# wind_turbine_sc.net
KiCad netlist of a schematic drawn in EAGLE
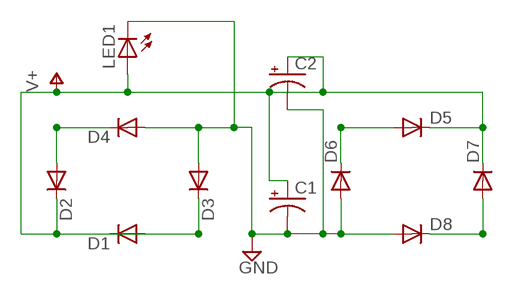
[diagram p0: schematic, sheet 1]

(export (version "E")
  (design (tool "Eeschema 10.0.6"))
  (components
    (comp (ref "C1")
      (value "CAP_POLPTH4")
      (footprint "eagle-import:CPOL-RADIAL-1000UF-25V")
      (libsource (lib "eagle-import") (part "CAP_POLPTH4"))
    )
    (comp (ref "C2")
      (value "CAP_POLPTH4")
      (footprint "eagle-import:CPOL-RADIAL-1000UF-25V")
      (libsource (lib "eagle-import") (part "CAP_POLPTH4"))
    )
    (comp (ref "D1")
      (value "DIODE1N4148")
      (footprint "eagle-import:DIODE-1N4148")
      (libsource (lib "eagle-import") (part "DIODE1N4148"))
    )
    (comp (ref "D2")
      (value "DIODE1N4148")
      (footprint "eagle-import:DIODE-1N4148")
      (libsource (lib "eagle-import") (part "DIODE1N4148"))
    )
    (comp (ref "D3")
      (value "DIODE1N4148")
      (footprint "eagle-import:DIODE-1N4148")
      (libsource (lib "eagle-import") (part "DIODE1N4148"))
    )
    (comp (ref "D4")
      (value "DIODE1N4148")
      (footprint "eagle-import:DIODE-1N4148")
      (libsource (lib "eagle-import") (part "DIODE1N4148"))
    )
    (comp (ref "D5")
      (value "DIODE1N4148")
      (footprint "eagle-import:DIODE-1N4148")
      (libsource (lib "eagle-import") (part "DIODE1N4148"))
    )
    (comp (ref "D6")
      (value "DIODE1N4148")
      (footprint "eagle-import:DIODE-1N4148")
      (libsource (lib "eagle-import") (part "DIODE1N4148"))
    )
    (comp (ref "D7")
      (value "DIODE1N4148")
      (footprint "eagle-import:DIODE-1N4148")
      (libsource (lib "eagle-import") (part "DIODE1N4148"))
    )
    (comp (ref "D8")
      (value "DIODE1N4148")
      (footprint "eagle-import:DIODE-1N4148")
      (libsource (lib "eagle-import") (part "DIODE1N4148"))
    )
    (comp (ref "LED1")
      (value "LED5MM")
      (footprint "eagle-import:LED5MM")
      (libsource (lib "eagle-import") (part "LED5MM"))
    )
  )
  (nets
    (net (code "1") (name "GND") (class "Default")
      (node (ref "C1") (pin "2") (pinfunction "-_2") (pintype "passive"))
      (node (ref "C2") (pin "2") (pinfunction "-_2") (pintype "passive"))
      (node (ref "D3") (pin "A") (pinfunction "A_A") (pintype "passive"))
      (node (ref "D4") (pin "A") (pinfunction "A_A") (pintype "passive"))
      (node (ref "D6") (pin "A") (pinfunction "A_A") (pintype "passive"))
      (node (ref "D8") (pin "A") (pinfunction "A_A") (pintype "passive"))
      (node (ref "LED1") (pin "K") (pinfunction "C_K") (pintype "passive"))
    )
    (net (code "2") (name "Net-(D1-PadA)") (class "Default")
      (node (ref "D1") (pin "A") (pinfunction "A_A") (pintype "passive"))
      (node (ref "D1") (pin "C") (pinfunction "C_C") (pintype "passive"))
    )
    (net (code "3") (name "Net-(D2-PadA)") (class "Default")
      (node (ref "D2") (pin "A") (pinfunction "A_A") (pintype "passive"))
      (node (ref "D4") (pin "C") (pinfunction "C_C") (pintype "passive"))
    )
    (net (code "4") (name "Net-(D5-PadA)") (class "Default")
      (node (ref "D5") (pin "A") (pinfunction "A_A") (pintype "passive"))
      (node (ref "D6") (pin "C") (pinfunction "C_C") (pintype "passive"))
    )
    (net (code "5") (name "Net-(D7-PadA)") (class "Default")
      (node (ref "D7") (pin "A") (pinfunction "A_A") (pintype "passive"))
      (node (ref "D8") (pin "C") (pinfunction "C_C") (pintype "passive"))
    )
    (net (code "6") (name "V+") (class "Default")
      (node (ref "C1") (pin "1") (pinfunction "+_1") (pintype "passive"))
      (node (ref "C2") (pin "1") (pinfunction "+_1") (pintype "passive"))
      (node (ref "D2") (pin "C") (pinfunction "C_C") (pintype "passive"))
      (node (ref "D3") (pin "C") (pinfunction "C_C") (pintype "passive"))
      (node (ref "D5") (pin "C") (pinfunction "C_C") (pintype "passive"))
      (node (ref "D7") (pin "C") (pinfunction "C_C") (pintype "passive"))
      (node (ref "LED1") (pin "A") (pinfunction "A_A") (pintype "passive"))
    )
  )
)
